# CH32V007E8R6.net
KiCad netlist of a schematic drawn in Altium Designer
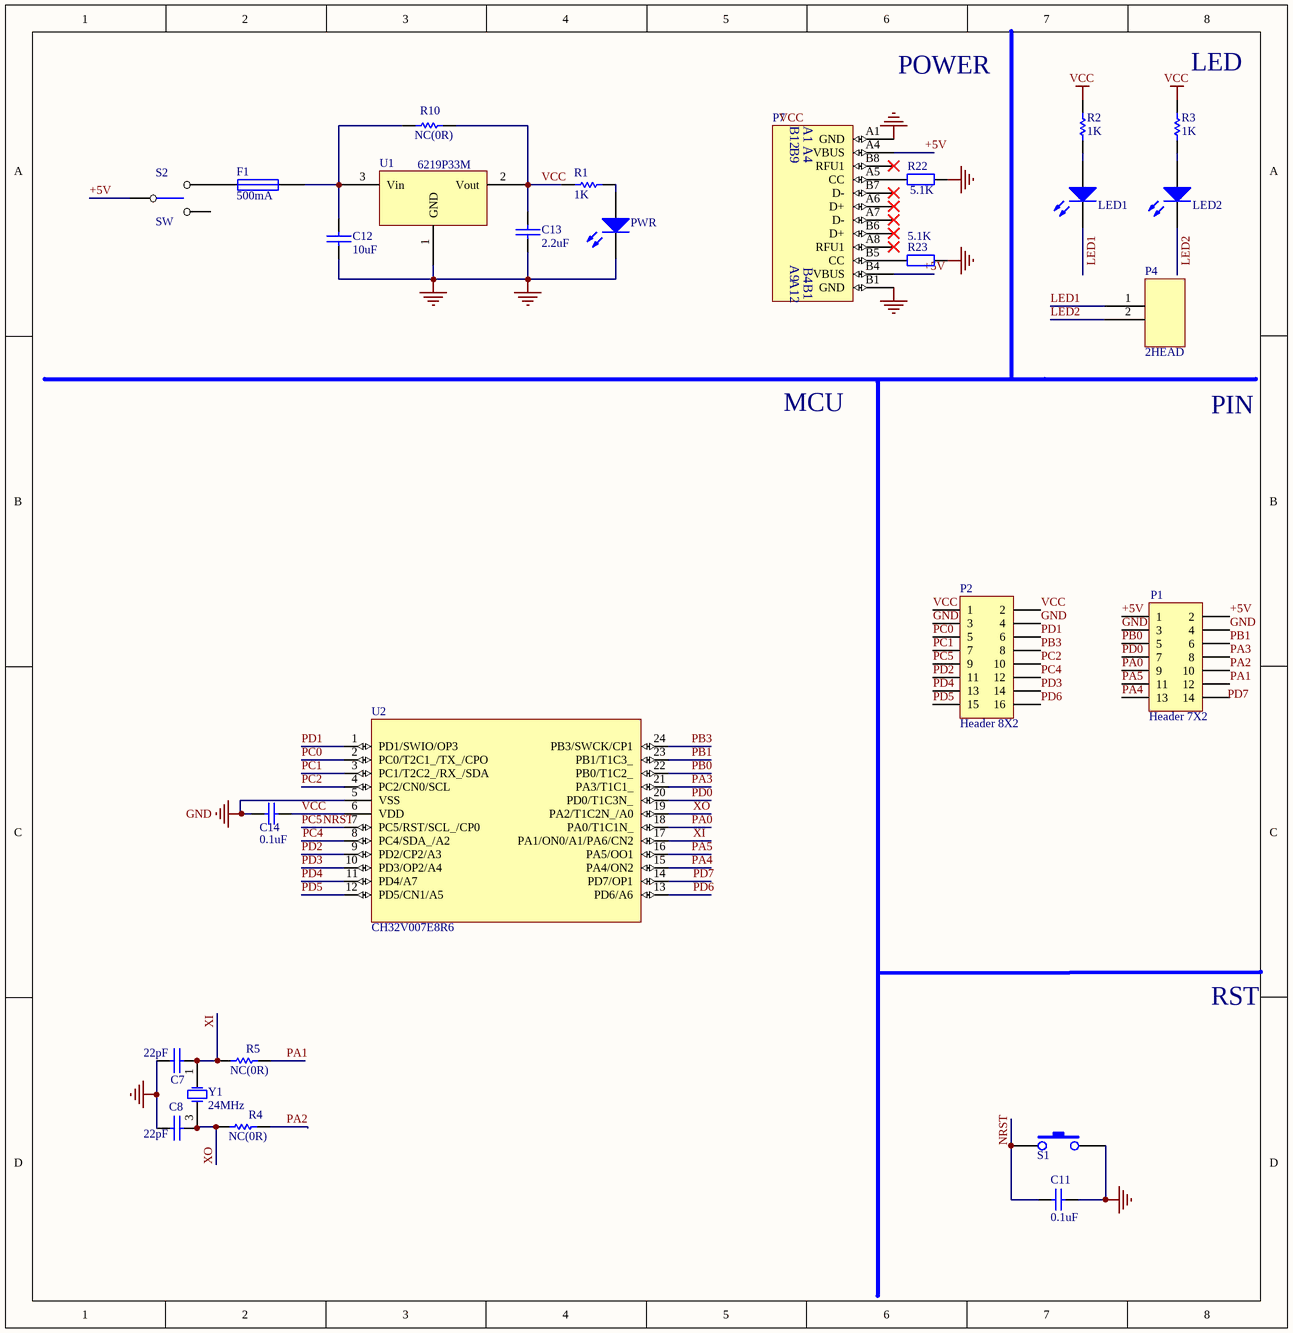
[diagram p0: CH32V007E8R6.SchDoc]

(export (version "E")
  (design (tool "Eeschema 10.0.6"))
  (components
    (comp (ref "C7")
      (value "22pF")
      (footprint "0402_C")
      (description "Capacitor")
      (libsource (lib "*") (part "CAP"))
    )
    (comp (ref "C8")
      (value "22pF")
      (footprint "0402_C")
      (description "Capacitor")
      (libsource (lib "*") (part "CAP"))
    )
    (comp (ref "C11")
      (value "0.1uF")
      (footprint "0402_C")
      (description "Capacitor")
      (fields (field (name "PUBLISHER") "Altium Limited"))
      (libsource (lib "*") (part "Cap"))
    )
    (comp (ref "C12")
      (value "10uF")
      (footprint "0603_C")
      (description "Capacitor")
      (libsource (lib "wch_sch_others") (part "CAP"))
    )
    (comp (ref "C13")
      (value "2.2uF")
      (footprint "0402_C")
      (description "Capacitor")
      (libsource (lib "wch_sch_others") (part "CAP"))
    )
    (comp (ref "C14")
      (value "0.1uF")
      (footprint "0603_C")
      (description "Capacitor")
      (fields (field (name "PUBLISHER") "Altium Limited"))
      (libsource (lib "*") (part "Cap"))
    )
    (comp (ref "F1")
      (value "500mA")
      (footprint "0603")
      (description "Fuse")
      (libsource (lib "*") (part "FUSE1"))
    )
    (comp (ref "LED1")
      (value "LED1   blue")
      (footprint "0603+")
      (description "Typical INFRARED GaAs LED")
      (fields (field (name "PUBLISHER") "Altium Limited"))
      (libsource (lib "*") (part "LED0"))
    )
    (comp (ref "LED2")
      (value "LED2  blue")
      (footprint "0603+")
      (description "Typical INFRARED GaAs LED")
      (fields (field (name "PUBLISHER") "Altium Limited"))
      (libsource (lib "*") (part "LED0"))
    )
    (comp (ref "P1")
      (value "Header 7X2")
      (footprint "HDR2X7")
      (description "Header, 7-Pin, Dual row")
      (fields (field (name "PUBLISHER") "Altium Limited"))
      (libsource (lib "Miscellaneous Connectors") (part "Header 7X2"))
    )
    (comp (ref "P2")
      (value "Header 8X2")
      (footprint "HDR2X8")
      (description "Header, 8-Pin, Dual row")
      (fields (field (name "PUBLISHER") "Altium Limited"))
      (libsource (lib "Miscellaneous Connectors") (part "Header 8X2"))
    )
    (comp (ref "P4") (value "2HEAD") (footprint "SIP2-2.54mm") (libsource (lib "*") (part "2HEAD")))
    (comp (ref "P7")
      (value "TYPE-C")
      (footprint "TYPE-C-Receptacle-2.0")
      (libsource (lib "*") (part "TYPE-C1"))
    )
    (comp (ref "PWR")
      (value "POWER  red")
      (footprint "0603+")
      (description "Typical INFRARED GaAs LED")
      (fields (field (name "PUBLISHER") "Altium Limited"))
      (libsource (lib "") (part "LED0_1"))
    )
    (comp (ref "R1")
      (value "1K")
      (footprint "0402")
      (description "Semiconductor Resistor")
      (fields (field (name "PUBLISHER") "Altium Limited"))
      (libsource (lib "*") (part "Res Semi"))
    )
    (comp (ref "R2")
      (value "1K")
      (footprint "0402")
      (description "Semiconductor Resistor")
      (fields (field (name "PUBLISHER") "Altium Limited"))
      (libsource (lib "*") (part "Res Semi"))
    )
    (comp (ref "R3")
      (value "1K")
      (footprint "0402")
      (description "Semiconductor Resistor")
      (fields (field (name "PUBLISHER") "Altium Limited"))
      (libsource (lib "*") (part "Res Semi"))
    )
    (comp (ref "R4")
      (value "NC(0R)")
      (footprint "0402")
      (description "Semiconductor Resistor")
      (fields (field (name "Comment") "0R") (field (name "PUBLISHER") "Altium Limited"))
      (libsource (lib "*") (part "Res Semi"))
    )
    (comp (ref "R5")
      (value "NC(0R)")
      (footprint "0402")
      (description "Semiconductor Resistor")
      (fields (field (name "Comment") "0R") (field (name "PUBLISHER") "Altium Limited"))
      (libsource (lib "*") (part "Res Semi"))
    )
    (comp (ref "R10")
      (value "NC(0R)")
      (footprint "0402")
      (description "Semiconductor Resistor")
      (fields (field (name "Comment") "0R") (field (name "PUBLISHER") "Altium Limited"))
      (libsource (lib "*") (part "Res Semi"))
    )
    (comp (ref "R22")
      (value "5.1K")
      (footprint "0402")
      (description "Resistor")
      (libsource (lib "Miscellaneous Devices") (part "Res2"))
    )
    (comp (ref "R23")
      (value "5.1K")
      (footprint "0402")
      (description "Resistor")
      (libsource (lib "Miscellaneous Devices") (part "Res2"))
    )
    (comp (ref "S1") (value "NRST") (footprint "SMD_6.1x3.65x2.5mm-KEY") (libsource (lib "*") (part "KEY")))
    (comp (ref "S2") (value "SW") (footprint "SW1") (libsource (lib "*") (part "SW")))
    (comp (ref "U1")
      (value "6219P33M")
      (footprint "SOT-23")
      (libsource (lib "wch_sch_others") (part "6219P33M"))
    )
    (comp (ref "U2")
      (value "CH32V007E8R6")
      (footprint "QSOP24")
      (description "RISC-V MCU, ADC/OPA/CMP/2*UART/I2C/SPI")
      (libsource (lib "DHXXXSCH") (part "CH32V007E8R6"))
    )
    (comp (ref "Y1")
      (value "24MHz")
      (footprint "XT3225")
      (description "Crystal Oscillator")
      (fields (field (name "PUBLISHER") "Altium Limited"))
      (libsource (lib "*") (part "XTAL"))
    )
  )
  (nets
    (net (code "1") (name "/+5V") (class "Default")
      (node (ref "P1") (pin "1") (pinfunction "1_1") (pintype "passive"))
      (node (ref "P1") (pin "2") (pinfunction "2_2") (pintype "passive"))
      (node (ref "P7") (pin "A4") (pinfunction "VBUS_A4") (pintype "bidirectional"))
      (node (ref "P7") (pin "B4") (pinfunction "VBUS_B4") (pintype "bidirectional"))
      (node (ref "S2") (pin "1") (pinfunction "1_1") (pintype "passive"))
    )
    (net (code "2") (name "/LED1") (class "Default")
      (node (ref "LED1") (pin "2") (pinfunction "K_2") (pintype "passive"))
      (node (ref "P4") (pin "1") (pintype "passive"))
    )
    (net (code "3") (name "/LED2") (class "Default")
      (node (ref "LED2") (pin "2") (pinfunction "K_2") (pintype "passive"))
      (node (ref "P4") (pin "2") (pintype "passive"))
    )
    (net (code "4") (name "/NRST") (class "Default")
      (node (ref "C11") (pin "2") (pinfunction "2_2") (pintype "passive"))
      (node (ref "P2") (pin "9") (pinfunction "9_9") (pintype "passive"))
      (node (ref "S1") (pin "1") (pinfunction "1_1") (pintype "passive"))
      (node (ref "U2") (pin "7") (pinfunction "PC5/RST/SCL_/CP0_7") (pintype "bidirectional"))
    )
    (net (code "5") (name "/PA0") (class "Default")
      (node (ref "P1") (pin "9") (pinfunction "9_9") (pintype "passive"))
      (node (ref "U2") (pin "18") (pinfunction "PA0/T1C1N__18") (pintype "bidirectional"))
    )
    (net (code "6") (name "/PA1") (class "Default")
      (node (ref "P1") (pin "12") (pinfunction "12_12") (pintype "passive"))
      (node (ref "R5") (pin "2") (pinfunction "2_2") (pintype "passive"))
    )
    (net (code "7") (name "/PA2") (class "Default")
      (node (ref "P1") (pin "10") (pinfunction "10_10") (pintype "passive"))
      (node (ref "R4") (pin "2") (pinfunction "2_2") (pintype "passive"))
    )
    (net (code "8") (name "/PA3") (class "Default")
      (node (ref "P1") (pin "8") (pinfunction "8_8") (pintype "passive"))
      (node (ref "U2") (pin "21") (pinfunction "PA3/T1C1__21") (pintype "bidirectional"))
    )
    (net (code "9") (name "/PA4") (class "Default")
      (node (ref "P1") (pin "13") (pinfunction "13_13") (pintype "passive"))
      (node (ref "U2") (pin "15") (pinfunction "PA4/ON2_15") (pintype "bidirectional"))
    )
    (net (code "10") (name "/PA5") (class "Default")
      (node (ref "P1") (pin "11") (pinfunction "11_11") (pintype "passive"))
      (node (ref "U2") (pin "16") (pinfunction "PA5/OO1_16") (pintype "bidirectional"))
    )
    (net (code "11") (name "/PB0") (class "Default")
      (node (ref "P1") (pin "5") (pinfunction "5_5") (pintype "passive"))
      (node (ref "U2") (pin "22") (pinfunction "PB0/T1C2__22") (pintype "bidirectional"))
    )
    (net (code "12") (name "/PB1") (class "Default")
      (node (ref "P1") (pin "6") (pinfunction "6_6") (pintype "passive"))
      (node (ref "U2") (pin "23") (pinfunction "PB1/T1C3__23") (pintype "bidirectional"))
    )
    (net (code "13") (name "/PB3") (class "Default")
      (node (ref "P2") (pin "8") (pinfunction "8_8") (pintype "passive"))
      (node (ref "U2") (pin "24") (pinfunction "PB3/SWCK/CP1_24") (pintype "bidirectional"))
    )
    (net (code "14") (name "/PC0") (class "Default")
      (node (ref "P2") (pin "5") (pinfunction "5_5") (pintype "passive"))
      (node (ref "U2") (pin "2") (pinfunction "PC0/T2C1_/TX_/CPO_2") (pintype "bidirectional"))
    )
    (net (code "15") (name "/PC1") (class "Default")
      (node (ref "P2") (pin "7") (pinfunction "7_7") (pintype "passive"))
      (node (ref "U2") (pin "3") (pinfunction "PC1/T2C2_/RX_/SDA_3") (pintype "bidirectional"))
    )
    (net (code "16") (name "/PC2") (class "Default")
      (node (ref "P2") (pin "10") (pinfunction "10_10") (pintype "passive"))
      (node (ref "U2") (pin "4") (pinfunction "PC2/CN0/SCL_4") (pintype "bidirectional"))
    )
    (net (code "17") (name "/PC4") (class "Default")
      (node (ref "P2") (pin "12") (pinfunction "12_12") (pintype "passive"))
      (node (ref "U2") (pin "8") (pinfunction "PC4/SDA_/A2_8") (pintype "bidirectional"))
    )
    (net (code "18") (name "/PD0") (class "Default")
      (node (ref "P1") (pin "7") (pinfunction "7_7") (pintype "passive"))
      (node (ref "U2") (pin "20") (pinfunction "PD0/T1C3N__20") (pintype "bidirectional"))
    )
    (net (code "19") (name "/PD1") (class "Default")
      (node (ref "P2") (pin "6") (pinfunction "6_6") (pintype "passive"))
      (node (ref "U2") (pin "1") (pinfunction "PD1/SWIO/OP3_1") (pintype "bidirectional"))
    )
    (net (code "20") (name "/PD2") (class "Default")
      (node (ref "P2") (pin "11") (pinfunction "11_11") (pintype "passive"))
      (node (ref "U2") (pin "9") (pinfunction "PD2/CP2/A3_9") (pintype "bidirectional"))
    )
    (net (code "21") (name "/PD3") (class "Default")
      (node (ref "P2") (pin "14") (pinfunction "14_14") (pintype "passive"))
      (node (ref "U2") (pin "10") (pinfunction "PD3/OP2/A4_10") (pintype "bidirectional"))
    )
    (net (code "22") (name "/PD4") (class "Default")
      (node (ref "P2") (pin "13") (pinfunction "13_13") (pintype "passive"))
      (node (ref "U2") (pin "11") (pinfunction "PD4/A7_11") (pintype "bidirectional"))
    )
    (net (code "23") (name "/PD5") (class "Default")
      (node (ref "P2") (pin "15") (pinfunction "15_15") (pintype "passive"))
      (node (ref "U2") (pin "12") (pinfunction "PD5/CN1/A5_12") (pintype "bidirectional"))
    )
    (net (code "24") (name "/PD6") (class "Default")
      (node (ref "P2") (pin "16") (pinfunction "16_16") (pintype "passive"))
      (node (ref "U2") (pin "13") (pinfunction "PD6/A6_13") (pintype "bidirectional"))
    )
    (net (code "25") (name "/PD7") (class "Default")
      (node (ref "U2") (pin "14") (pinfunction "PD7/OP1_14") (pintype "bidirectional"))
    )
    (net (code "26") (name "/XI") (class "Default")
      (node (ref "C7") (pin "2") (pinfunction "2_2") (pintype "passive"))
      (node (ref "R5") (pin "1") (pinfunction "1_1") (pintype "passive"))
      (node (ref "U2") (pin "17") (pinfunction "PA1/ON0/A1/PA6/CN2_17") (pintype "bidirectional"))
      (node (ref "Y1") (pin "1") (pinfunction "OSC1_1") (pintype "passive"))
    )
    (net (code "27") (name "/XO") (class "Default")
      (node (ref "C8") (pin "2") (pinfunction "2_2") (pintype "passive"))
      (node (ref "R4") (pin "1") (pinfunction "1_1") (pintype "passive"))
      (node (ref "U2") (pin "19") (pinfunction "PA2/T1C2N_/A0_19") (pintype "bidirectional"))
      (node (ref "Y1") (pin "3") (pinfunction "OSC2_3") (pintype "passive"))
    )
    (net (code "28") (name "GND") (class "Default")
      (node (ref "C11") (pin "1") (pinfunction "1_1") (pintype "passive"))
      (node (ref "C12") (pin "2") (pinfunction "2_2") (pintype "passive"))
      (node (ref "C13") (pin "1") (pinfunction "1_1") (pintype "passive"))
      (node (ref "C14") (pin "1") (pinfunction "1_1") (pintype "passive"))
      (node (ref "C7") (pin "1") (pinfunction "1_1") (pintype "passive"))
      (node (ref "C8") (pin "1") (pinfunction "1_1") (pintype "passive"))
      (node (ref "P1") (pin "3") (pinfunction "3_3") (pintype "passive"))
      (node (ref "P1") (pin "4") (pinfunction "4_4") (pintype "passive"))
      (node (ref "P2") (pin "3") (pinfunction "3_3") (pintype "passive"))
      (node (ref "P2") (pin "4") (pinfunction "4_4") (pintype "passive"))
      (node (ref "P7") (pin "A1") (pinfunction "GND_A1") (pintype "bidirectional"))
      (node (ref "P7") (pin "B1") (pinfunction "GND_B1") (pintype "bidirectional"))
      (node (ref "PWR") (pin "2") (pinfunction "K_2") (pintype "passive"))
      (node (ref "R22") (pin "2") (pinfunction "2_2") (pintype "passive"))
      (node (ref "R23") (pin "2") (pinfunction "2_2") (pintype "passive"))
      (node (ref "S1") (pin "2") (pinfunction "2_2") (pintype "passive"))
      (node (ref "U1") (pin "1") (pinfunction "GND_1") (pintype "passive"))
      (node (ref "U2") (pin "5") (pinfunction "VSS_5") (pintype "power_in"))
    )
    (net (code "29") (name "Net-(F1-Pad1)") (class "Default")
      (node (ref "F1") (pin "1") (pinfunction "1_1") (pintype "passive"))
      (node (ref "S2") (pin "3") (pinfunction "3_3") (pintype "passive"))
    )
    (net (code "30") (name "Net-(LED1-A)") (class "Default")
      (node (ref "LED1") (pin "1") (pinfunction "A_1") (pintype "passive"))
      (node (ref "R2") (pin "2") (pinfunction "2_2") (pintype "passive"))
    )
    (net (code "31") (name "Net-(LED2-A)") (class "Default")
      (node (ref "LED2") (pin "1") (pinfunction "A_1") (pintype "passive"))
      (node (ref "R3") (pin "2") (pinfunction "2_2") (pintype "passive"))
    )
    (net (code "32") (name "Net-(P7-CC-PadA5)") (class "Default")
      (node (ref "P7") (pin "A5") (pinfunction "CC_A5") (pintype "bidirectional"))
      (node (ref "R22") (pin "1") (pinfunction "1_1") (pintype "passive"))
    )
    (net (code "33") (name "Net-(P7-CC-PadB5)") (class "Default")
      (node (ref "P7") (pin "B5") (pinfunction "CC_B5") (pintype "bidirectional"))
      (node (ref "R23") (pin "1") (pinfunction "1_1") (pintype "passive"))
    )
    (net (code "34") (name "Net-(PWR-A)") (class "Default")
      (node (ref "PWR") (pin "1") (pinfunction "A_1") (pintype "passive"))
      (node (ref "R1") (pin "1") (pinfunction "1_1") (pintype "passive"))
    )
    (net (code "35") (name "Net-(U1-Vin)") (class "Default")
      (node (ref "C12") (pin "1") (pinfunction "1_1") (pintype "passive"))
      (node (ref "F1") (pin "2") (pinfunction "2_2") (pintype "passive"))
      (node (ref "R10") (pin "1") (pinfunction "1_1") (pintype "passive"))
      (node (ref "U1") (pin "3") (pinfunction "Vin_3") (pintype "passive"))
    )
    (net (code "36") (name "VCC") (class "Default")
      (node (ref "C13") (pin "2") (pinfunction "2_2") (pintype "passive"))
      (node (ref "C14") (pin "2") (pinfunction "2_2") (pintype "passive"))
      (node (ref "P2") (pin "1") (pinfunction "1_1") (pintype "passive"))
      (node (ref "P2") (pin "2") (pinfunction "2_2") (pintype "passive"))
      (node (ref "R1") (pin "2") (pinfunction "2_2") (pintype "passive"))
      (node (ref "R10") (pin "2") (pinfunction "2_2") (pintype "passive"))
      (node (ref "R2") (pin "1") (pinfunction "1_1") (pintype "passive"))
      (node (ref "R3") (pin "1") (pinfunction "1_1") (pintype "passive"))
      (node (ref "U1") (pin "2") (pinfunction "Vout_2") (pintype "passive"))
      (node (ref "U2") (pin "6") (pinfunction "VDD_6") (pintype "power_in"))
    )
    (net (code "37") (name "unconnected-(P1-Pad14)") (class "Default")
      (node (ref "P1") (pin "14") (pinfunction "14_14") (pintype "passive"))
    )
    (net (code "38") (name "unconnected-(P7-D+-PadA6)") (class "Default")
      (node (ref "P7") (pin "A6") (pinfunction "D+_A6") (pintype "bidirectional+no_connect"))
    )
    (net (code "39") (name "unconnected-(P7-D+-PadB6)") (class "Default")
      (node (ref "P7") (pin "B6") (pinfunction "D+_B6") (pintype "bidirectional+no_connect"))
    )
    (net (code "40") (name "unconnected-(P7-D--PadA7)") (class "Default")
      (node (ref "P7") (pin "A7") (pinfunction "D-_A7") (pintype "bidirectional+no_connect"))
    )
    (net (code "41") (name "unconnected-(P7-D--PadB7)") (class "Default")
      (node (ref "P7") (pin "B7") (pinfunction "D-_B7") (pintype "bidirectional+no_connect"))
    )
    (net (code "42") (name "unconnected-(P7-RFU1-PadA8)") (class "Default")
      (node (ref "P7") (pin "A8") (pinfunction "RFU1_A8") (pintype "bidirectional+no_connect"))
    )
    (net (code "43") (name "unconnected-(P7-RFU1-PadB8)") (class "Default")
      (node (ref "P7") (pin "B8") (pinfunction "RFU1_B8") (pintype "bidirectional+no_connect"))
    )
    (net (code "44") (name "unconnected-(S2-Pad2)") (class "Default")
      (node (ref "S2") (pin "2") (pinfunction "2_2") (pintype "passive"))
    )
  )
)
